# Regulator.net
KiCad netlist of a schematic drawn in Altium Designer
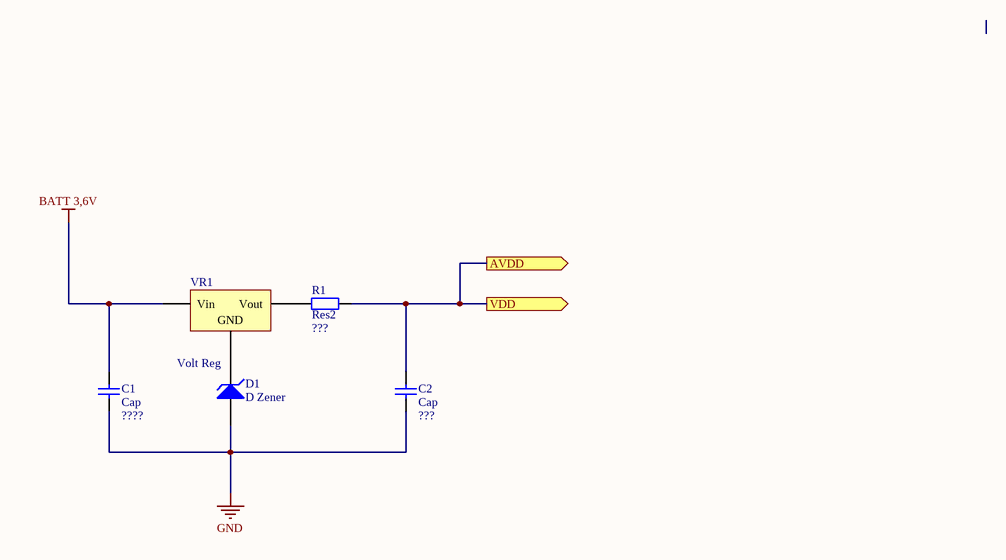
[diagram p0: Regulator.SchDoc]

(export (version "E")
  (design (tool "Eeschema 10.0.6"))
  (components
    (comp (ref "C1")
      (value "Cap")
      (footprint "RAD-0.3")
      (description "Capacitor")
      (fields (field (name "ALTIUM_VALUE") "????") (field (name "PUBLISHER") "Altium Limited"))
      (libsource (lib "Miscellaneous Devices") (part "Cap"))
    )
    (comp (ref "C2")
      (value "Cap")
      (footprint "RAD-0.3")
      (description "Capacitor")
      (fields (field (name "ALTIUM_VALUE") "???") (field (name "PUBLISHER") "Altium Limited"))
      (libsource (lib "Miscellaneous Devices") (part "Cap"))
    )
    (comp (ref "D1")
      (value "D Zener")
      (footprint "DIODE-0.7")
      (description "Zener Diode")
      (fields (field (name "PUBLISHER") "Altium Limited"))
      (libsource (lib "Miscellaneous Devices") (part "D Zener"))
    )
    (comp (ref "R1")
      (value "Res2")
      (footprint "AXIAL-0.4")
      (description "Resistor")
      (fields (field (name "ALTIUM_VALUE") "???") (field (name "PUBLISHER") "Altium Limited"))
      (libsource (lib "Miscellaneous Devices") (part "Res2"))
    )
    (comp (ref "VR1")
      (value "Volt Reg")
      (footprint "D2PAK_N")
      (description "Voltage Regulator")
      (fields (field (name "PUBLISHER") "Altium Limited"))
      (libsource (lib "Miscellaneous Devices") (part "Volt Reg"))
    )
  )
  (nets
    (net (code "1") (name "/AVDD") (class "Default")
      (node (ref "C2") (pin "2") (pinfunction "2_2") (pintype "passive"))
      (node (ref "R1") (pin "2") (pinfunction "2_2") (pintype "passive"))
    )
    (net (code "2") (name "BATT 3,6V") (class "Default")
      (node (ref "C1") (pin "2") (pinfunction "2_2") (pintype "passive"))
      (node (ref "VR1") (pin "1") (pinfunction "Vin_1") (pintype "passive"))
    )
    (net (code "3") (name "GND") (class "Default")
      (node (ref "C1") (pin "1") (pinfunction "1_1") (pintype "passive"))
      (node (ref "C2") (pin "1") (pinfunction "1_1") (pintype "passive"))
      (node (ref "D1") (pin "1") (pinfunction "A_1") (pintype "passive"))
    )
    (net (code "4") (name "Net-(D1-K)") (class "Default")
      (node (ref "D1") (pin "2") (pinfunction "K_2") (pintype "passive"))
      (node (ref "VR1") (pin "2") (pinfunction "GND_2") (pintype "passive"))
    )
    (net (code "5") (name "Net-(VR1-Vout)") (class "Default")
      (node (ref "R1") (pin "1") (pinfunction "1_1") (pintype "passive"))
      (node (ref "VR1") (pin "3") (pinfunction "Vout_3") (pintype "passive"))
    )
  )
)
